# Carrier-Board-CM740.net
KiCad netlist of a schematic drawn in EAGLE
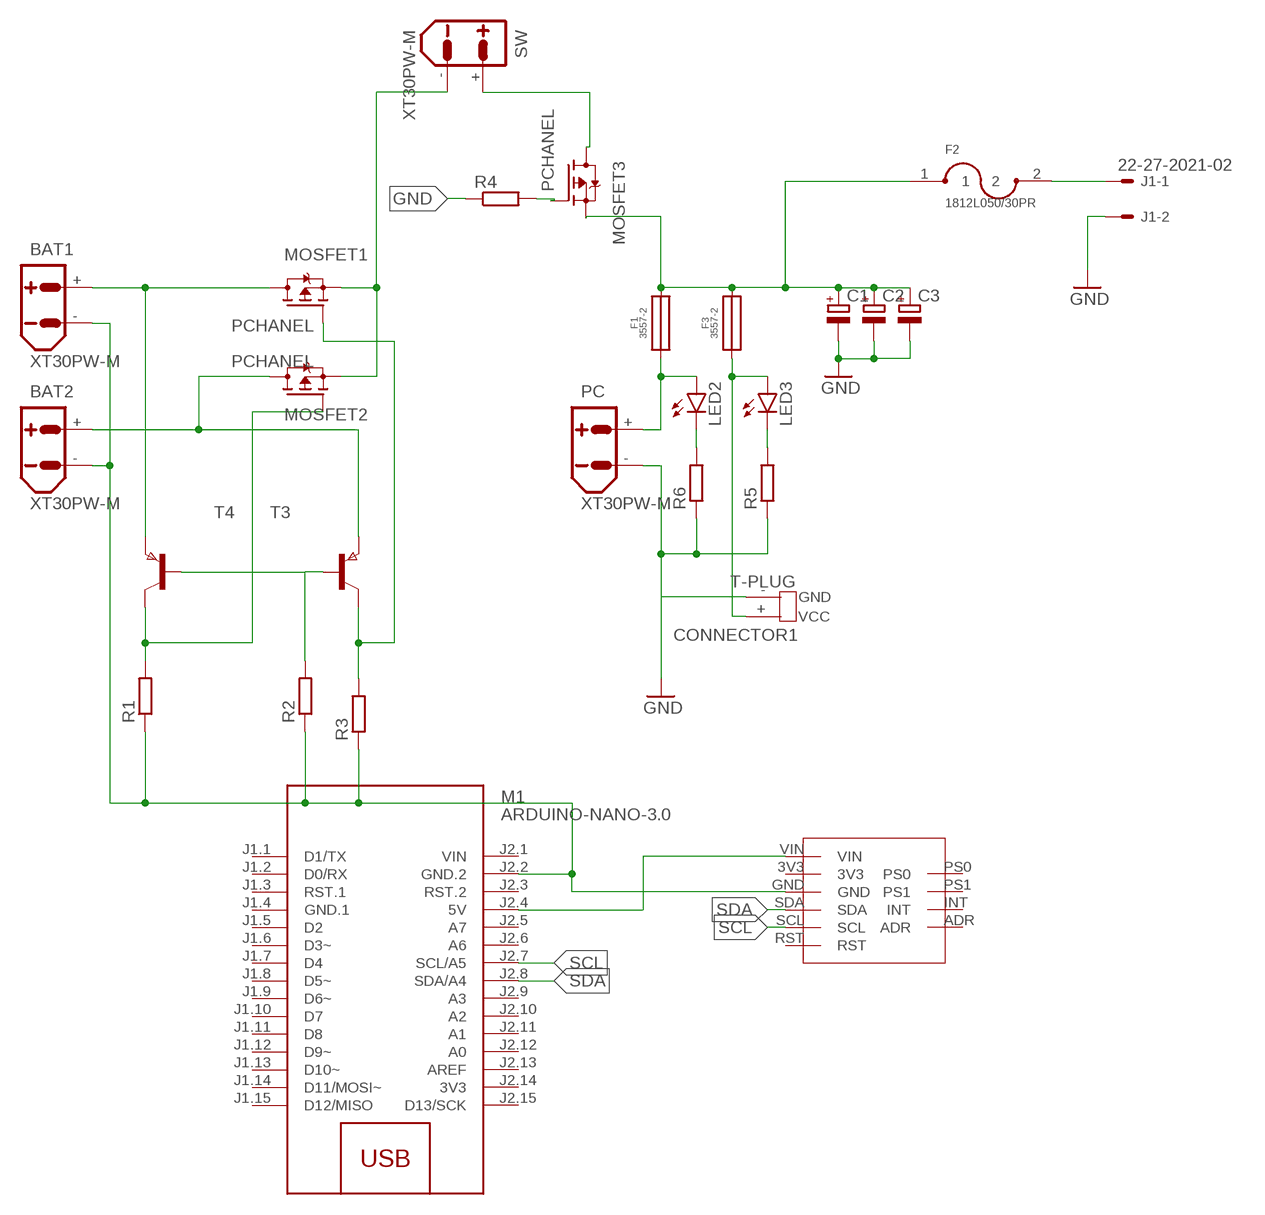
[diagram p0: schematic, sheet 1]

(export (version "E")
  (design (tool "Eeschema 10.0.6"))
  (components
    (comp (ref "BAT1")
      (value "XT30PW-M")
      (footprint "eagle-import:XT30PW-M")
      (libsource (lib "eagle-import") (part "XT30PW-M"))
    )
    (comp (ref "BAT2")
      (value "XT30PW-M")
      (footprint "eagle-import:XT30PW-M")
      (libsource (lib "eagle-import") (part "XT30PW-M"))
    )
    (comp (ref "C1")
      (value "CPOL-EU150CLZ-1014")
      (footprint "eagle-import:150CLZ-1014")
      (libsource (lib "eagle-import") (part "CPOL-EU150CLZ-1014"))
    )
    (comp (ref "C2")
      (value "CPOL-EU150CLZ-1014")
      (footprint "eagle-import:150CLZ-1014")
      (libsource (lib "eagle-import") (part "CPOL-EU150CLZ-1014"))
    )
    (comp (ref "C3")
      (value "CPOL-EU150CLZ-1014")
      (footprint "eagle-import:150CLZ-1014")
      (libsource (lib "eagle-import") (part "CPOL-EU150CLZ-1014"))
    )
    (comp (ref "CONNECTOR1")
      (value "T-PLUG")
      (footprint "eagle-import:T-PLUG")
      (libsource (lib "eagle-import") (part "T-PLUG"))
    )
    (comp (ref "F1")
      (value "3557-2")
      (footprint "eagle-import:3557-2")
      (libsource (lib "eagle-import") (part "3557-2"))
    )
    (comp (ref "F2")
      (value "1812L050/30PR")
      (footprint "eagle-import:FUSM4632X75")
      (fields (field (name "MF") "Littelfuse"))
      (libsource (lib "eagle-import") (part "1812L050/30PR"))
    )
    (comp (ref "F3")
      (value "3557-2")
      (footprint "eagle-import:3557-2")
      (libsource (lib "eagle-import") (part "3557-2"))
    )
    (comp (ref "J1")
      (value "22-27-2021-02")
      (footprint "eagle-import:6410-02")
      (fields (field (name "MF") "MOLEX"))
      (libsource (lib "eagle-import") (part "22-?-0227-2021"))
    )
    (comp (ref "LED2")
      (value "LEDCHIP-LED0805")
      (footprint "eagle-import:CHIP-LED0805")
      (libsource (lib "eagle-import") (part "LEDCHIP-LED0805"))
    )
    (comp (ref "LED3")
      (value "LEDCHIP-LED0805")
      (footprint "eagle-import:CHIP-LED0805")
      (libsource (lib "eagle-import") (part "LEDCHIP-LED0805"))
    )
    (comp (ref "M1")
      (value "ARDUINO-NANO-3.0")
      (footprint "eagle-import:ARDUINO-NANO-3.0")
      (libsource (lib "eagle-import") (part "ARDUINO-NANO-3.0"))
    )
    (comp (ref "MOSFET1")
      (value "PCHANEL")
      (footprint "eagle-import:TO252")
      (libsource (lib "eagle-import") (part "FDD4141TO252"))
    )
    (comp (ref "MOSFET2")
      (value "PCHANEL")
      (footprint "eagle-import:TO252")
      (libsource (lib "eagle-import") (part "FDD4141TO252"))
    )
    (comp (ref "MOSFET3")
      (value "PCHANEL")
      (footprint "eagle-import:TO252")
      (libsource (lib "eagle-import") (part "FDD4141TO252"))
    )
    (comp (ref "PC")
      (value "XT30PW-M")
      (footprint "eagle-import:XT30PW-M")
      (libsource (lib "eagle-import") (part "XT30PW-M"))
    )
    (comp (ref "R1")
      (value "R-EU_R1206")
      (footprint "eagle-import:R1206")
      (libsource (lib "eagle-import") (part "R-EU_R1206"))
    )
    (comp (ref "R2")
      (value "R-EU_R1206")
      (footprint "eagle-import:R1206")
      (libsource (lib "eagle-import") (part "R-EU_R1206"))
    )
    (comp (ref "R3")
      (value "R-EU_R1206")
      (footprint "eagle-import:R1206")
      (libsource (lib "eagle-import") (part "R-EU_R1206"))
    )
    (comp (ref "R4")
      (value "R-EU_R1206")
      (footprint "eagle-import:R1206")
      (libsource (lib "eagle-import") (part "R-EU_R1206"))
    )
    (comp (ref "R5")
      (value "R-EU_M0805")
      (footprint "eagle-import:M0805")
      (libsource (lib "eagle-import") (part "R-EU_M0805"))
    )
    (comp (ref "R6")
      (value "R-EU_M0805")
      (footprint "eagle-import:M0805")
      (libsource (lib "eagle-import") (part "R-EU_M0805"))
    )
    (comp (ref "SW")
      (value "XT30PW-M")
      (footprint "eagle-import:XT30PW-M")
      (libsource (lib "eagle-import") (part "XT30PW-M"))
    )
    (comp (ref "T3")
      (value "PNPSOT23")
      (footprint "eagle-import:SOT-23")
      (fields (field (name "MPN") "DSS20200L-7"))
      (libsource (lib "eagle-import") (part "PNPSOT23"))
    )
    (comp (ref "T4")
      (value "PNPSOT23")
      (footprint "eagle-import:SOT-23")
      (fields (field (name "MPN") "DSS20200L-7"))
      (libsource (lib "eagle-import") (part "PNPSOT23"))
    )
    (comp (ref "U$1")
      (value "BNO055_BNO055")
      (footprint "eagle-import:BNO055_BNO055")
      (libsource (lib "eagle-import") (part "BNO055_BNO055"))
    )
  )
  (nets
    (net (code "1") (name "/3V3") (class "Default")
      (node (ref "M1") (pin "J2.14") (pinfunction "3V3_J2.14") (pintype "power_in"))
    )
    (net (code "2") (name "/GND.1") (class "Default")
      (node (ref "M1") (pin "J1.4") (pinfunction "GND.1_J1.4") (pintype "power_in"))
    )
    (net (code "3") (name "/VIN") (class "Default")
      (node (ref "M1") (pin "J2.1") (pinfunction "VIN_J2.1") (pintype "power_in"))
    )
    (net (code "4") (name "GND") (class "Default")
      (node (ref "BAT1") (pin "-") (pinfunction "-_-") (pintype "power_in"))
      (node (ref "BAT2") (pin "-") (pinfunction "-_-") (pintype "power_in"))
      (node (ref "C1") (pin "-") (pinfunction "-_-") (pintype "passive"))
      (node (ref "C2") (pin "-") (pinfunction "-_-") (pintype "passive"))
      (node (ref "C3") (pin "-") (pinfunction "-_-") (pintype "passive"))
      (node (ref "CONNECTOR1") (pin "-") (pinfunction "GND_-") (pintype "power_in"))
      (node (ref "J1") (pin "2") (pinfunction "S_2") (pintype "passive"))
      (node (ref "M1") (pin "J2.2") (pinfunction "GND.2_J2.2") (pintype "power_in"))
      (node (ref "PC") (pin "-") (pinfunction "-_-") (pintype "power_in"))
      (node (ref "R1") (pin "1") (pinfunction "1_1") (pintype "passive"))
      (node (ref "R2") (pin "1") (pinfunction "1_1") (pintype "passive"))
      (node (ref "R3") (pin "1") (pinfunction "1_1") (pintype "passive"))
      (node (ref "R4") (pin "1") (pinfunction "1_1") (pintype "passive"))
      (node (ref "R5") (pin "1") (pinfunction "1_1") (pintype "passive"))
      (node (ref "R6") (pin "1") (pinfunction "1_1") (pintype "passive"))
      (node (ref "U$1") (pin "GND") (pinfunction "GND_GND") (pintype "bidirectional"))
    )
    (net (code "5") (name "Net-(CONNECTOR1-VCC)") (class "Default")
      (node (ref "CONNECTOR1") (pin "+") (pinfunction "VCC_+") (pintype "power_in"))
      (node (ref "F3") (pin "1") (pinfunction "1_1") (pintype "bidirectional"))
      (node (ref "F3") (pin "2") (pinfunction "1_2") (pintype "bidirectional"))
      (node (ref "LED3") (pin "A") (pinfunction "A_A") (pintype "passive"))
    )
    (net (code "6") (name "Net-(F1-1-Pad2)") (class "Default")
      (node (ref "F1") (pin "1") (pinfunction "1_1") (pintype "bidirectional"))
      (node (ref "F1") (pin "2") (pinfunction "1_2") (pintype "bidirectional"))
      (node (ref "LED2") (pin "A") (pinfunction "A_A") (pintype "passive"))
      (node (ref "PC") (pin "+") (pinfunction "+_+") (pintype "power_in"))
    )
    (net (code "7") (name "Net-(J1A-S)") (class "Default")
      (node (ref "F2") (pin "2") (pinfunction "2_2") (pintype "passive"))
      (node (ref "J1") (pin "1") (pinfunction "S_1") (pintype "passive"))
    )
    (net (code "8") (name "Net-(LED2-PadC)") (class "Default")
      (node (ref "LED2") (pin "C") (pinfunction "C_C") (pintype "passive"))
      (node (ref "R6") (pin "2") (pinfunction "2_2") (pintype "passive"))
    )
    (net (code "9") (name "Net-(LED3-PadC)") (class "Default")
      (node (ref "LED3") (pin "C") (pinfunction "C_C") (pintype "passive"))
      (node (ref "R5") (pin "2") (pinfunction "2_2") (pintype "passive"))
    )
    (net (code "10") (name "Net-(M1-5V)") (class "Default")
      (node (ref "M1") (pin "J2.4") (pinfunction "5V_J2.4") (pintype "power_in"))
      (node (ref "U$1") (pin "VIN") (pinfunction "VIN_VIN") (pintype "bidirectional"))
    )
    (net (code "11") (name "Net-(MOSFET1-D)") (class "Default")
      (node (ref "BAT1") (pin "+") (pinfunction "+_+") (pintype "power_in"))
      (node (ref "MOSFET1") (pin "3") (pinfunction "D_3") (pintype "passive"))
      (node (ref "T4") (pin "2") (pinfunction "E_2") (pintype "passive"))
    )
    (net (code "12") (name "Net-(MOSFET1-G)") (class "Default")
      (node (ref "MOSFET1") (pin "1") (pinfunction "G_1") (pintype "passive"))
      (node (ref "R3") (pin "2") (pinfunction "2_2") (pintype "passive"))
      (node (ref "T3") (pin "1") (pinfunction "C_1") (pintype "passive"))
    )
    (net (code "13") (name "Net-(MOSFET1-S)") (class "Default")
      (node (ref "MOSFET1") (pin "2") (pinfunction "S_2") (pintype "passive"))
      (node (ref "MOSFET2") (pin "2") (pinfunction "S_2") (pintype "passive"))
      (node (ref "SW") (pin "-") (pinfunction "-_-") (pintype "power_in"))
    )
    (net (code "14") (name "Net-(MOSFET2-D)") (class "Default")
      (node (ref "BAT2") (pin "+") (pinfunction "+_+") (pintype "power_in"))
      (node (ref "MOSFET2") (pin "3") (pinfunction "D_3") (pintype "passive"))
      (node (ref "T3") (pin "2") (pinfunction "E_2") (pintype "passive"))
    )
    (net (code "15") (name "Net-(MOSFET2-G)") (class "Default")
      (node (ref "MOSFET2") (pin "1") (pinfunction "G_1") (pintype "passive"))
      (node (ref "R1") (pin "2") (pinfunction "2_2") (pintype "passive"))
      (node (ref "T4") (pin "1") (pinfunction "C_1") (pintype "passive"))
    )
    (net (code "16") (name "Net-(MOSFET3-D)") (class "Default")
      (node (ref "MOSFET3") (pin "3") (pinfunction "D_3") (pintype "passive"))
      (node (ref "SW") (pin "+") (pinfunction "+_+") (pintype "power_in"))
    )
    (net (code "17") (name "Net-(MOSFET3-G)") (class "Default")
      (node (ref "MOSFET3") (pin "1") (pinfunction "G_1") (pintype "passive"))
      (node (ref "R4") (pin "2") (pinfunction "2_2") (pintype "passive"))
    )
    (net (code "18") (name "Net-(MOSFET3-S)") (class "Default")
      (node (ref "C1") (pin "+") (pinfunction "+_+") (pintype "passive"))
      (node (ref "C2") (pin "+") (pinfunction "+_+") (pintype "passive"))
      (node (ref "C3") (pin "+") (pinfunction "+_+") (pintype "passive"))
      (node (ref "F1") (pin "3") (pinfunction "2_3") (pintype "bidirectional"))
      (node (ref "F1") (pin "4") (pinfunction "2_4") (pintype "bidirectional"))
      (node (ref "F2") (pin "1") (pinfunction "1_1") (pintype "passive"))
      (node (ref "F3") (pin "3") (pinfunction "2_3") (pintype "bidirectional"))
      (node (ref "F3") (pin "4") (pinfunction "2_4") (pintype "bidirectional"))
      (node (ref "MOSFET3") (pin "2") (pinfunction "S_2") (pintype "passive"))
    )
    (net (code "19") (name "Net-(T3-B)") (class "Default")
      (node (ref "R2") (pin "2") (pinfunction "2_2") (pintype "passive"))
      (node (ref "T3") (pin "3") (pinfunction "B_3") (pintype "passive"))
      (node (ref "T4") (pin "3") (pinfunction "B_3") (pintype "passive"))
    )
    (net (code "20") (name "SCL") (class "Default")
      (node (ref "M1") (pin "J2.7") (pinfunction "SCL/A5_J2.7") (pintype "bidirectional"))
      (node (ref "U$1") (pin "SCL") (pinfunction "SCL_SCL") (pintype "bidirectional"))
    )
    (net (code "21") (name "SDA") (class "Default")
      (node (ref "M1") (pin "J2.8") (pinfunction "SDA/A4_J2.8") (pintype "bidirectional"))
      (node (ref "U$1") (pin "SDA") (pinfunction "SDA_SDA") (pintype "bidirectional"))
    )
    (net (code "22") (name "unconnected-(M1-A0-PadJ2.12)") (class "Default")
      (node (ref "M1") (pin "J2.12") (pinfunction "A0_J2.12") (pintype "bidirectional"))
    )
    (net (code "23") (name "unconnected-(M1-A1-PadJ2.11)") (class "Default")
      (node (ref "M1") (pin "J2.11") (pinfunction "A1_J2.11") (pintype "bidirectional"))
    )
    (net (code "24") (name "unconnected-(M1-A2-PadJ2.10)") (class "Default")
      (node (ref "M1") (pin "J2.10") (pinfunction "A2_J2.10") (pintype "bidirectional"))
    )
    (net (code "25") (name "unconnected-(M1-A3-PadJ2.9)") (class "Default")
      (node (ref "M1") (pin "J2.9") (pinfunction "A3_J2.9") (pintype "bidirectional"))
    )
    (net (code "26") (name "unconnected-(M1-A6-PadJ2.6)") (class "Default")
      (node (ref "M1") (pin "J2.6") (pinfunction "A6_J2.6") (pintype "bidirectional"))
    )
    (net (code "27") (name "unconnected-(M1-A7-PadJ2.5)") (class "Default")
      (node (ref "M1") (pin "J2.5") (pinfunction "A7_J2.5") (pintype "bidirectional"))
    )
    (net (code "28") (name "unconnected-(M1-AREF-PadJ2.13)") (class "Default")
      (node (ref "M1") (pin "J2.13") (pinfunction "AREF_J2.13") (pintype "bidirectional"))
    )
    (net (code "29") (name "unconnected-(M1-D0{slash}RX-PadJ1.2)") (class "Default")
      (node (ref "M1") (pin "J1.2") (pinfunction "D0/RX_J1.2") (pintype "bidirectional"))
    )
    (net (code "30") (name "unconnected-(M1-D1{slash}TX-PadJ1.1)") (class "Default")
      (node (ref "M1") (pin "J1.1") (pinfunction "D1/TX_J1.1") (pintype "bidirectional"))
    )
    (net (code "31") (name "unconnected-(M1-D2-PadJ1.5)") (class "Default")
      (node (ref "M1") (pin "J1.5") (pinfunction "D2_J1.5") (pintype "bidirectional"))
    )
    (net (code "32") (name "unconnected-(M1-D3~{}-PadJ1.6)") (class "Default")
      (node (ref "M1") (pin "J1.6") (pinfunction "D3~{}_J1.6") (pintype "bidirectional"))
    )
    (net (code "33") (name "unconnected-(M1-D4-PadJ1.7)") (class "Default")
      (node (ref "M1") (pin "J1.7") (pinfunction "D4_J1.7") (pintype "bidirectional"))
    )
    (net (code "34") (name "unconnected-(M1-D5~{}-PadJ1.8)") (class "Default")
      (node (ref "M1") (pin "J1.8") (pinfunction "D5~{}_J1.8") (pintype "bidirectional"))
    )
    (net (code "35") (name "unconnected-(M1-D6~{}-PadJ1.9)") (class "Default")
      (node (ref "M1") (pin "J1.9") (pinfunction "D6~{}_J1.9") (pintype "bidirectional"))
    )
    (net (code "36") (name "unconnected-(M1-D7-PadJ1.10)") (class "Default")
      (node (ref "M1") (pin "J1.10") (pinfunction "D7_J1.10") (pintype "bidirectional"))
    )
    (net (code "37") (name "unconnected-(M1-D8-PadJ1.11)") (class "Default")
      (node (ref "M1") (pin "J1.11") (pinfunction "D8_J1.11") (pintype "bidirectional"))
    )
    (net (code "38") (name "unconnected-(M1-D9~{}-PadJ1.12)") (class "Default")
      (node (ref "M1") (pin "J1.12") (pinfunction "D9~{}_J1.12") (pintype "bidirectional"))
    )
    (net (code "39") (name "unconnected-(M1-D10~{}-PadJ1.13)") (class "Default")
      (node (ref "M1") (pin "J1.13") (pinfunction "D10~{}_J1.13") (pintype "bidirectional"))
    )
    (net (code "40") (name "unconnected-(M1-D11{slash}MOSI~{}-PadJ1.14)") (class "Default")
      (node (ref "M1") (pin "J1.14") (pinfunction "D11/MOSI~{}_J1.14") (pintype "bidirectional"))
    )
    (net (code "41") (name "unconnected-(M1-D12{slash}MISO-PadJ1.15)") (class "Default")
      (node (ref "M1") (pin "J1.15") (pinfunction "D12/MISO_J1.15") (pintype "bidirectional"))
    )
    (net (code "42") (name "unconnected-(M1-D13{slash}SCK-PadJ2.15)") (class "Default")
      (node (ref "M1") (pin "J2.15") (pinfunction "D13/SCK_J2.15") (pintype "bidirectional"))
    )
    (net (code "43") (name "unconnected-(M1-RST.1-PadJ1.3)") (class "Default")
      (node (ref "M1") (pin "J1.3") (pinfunction "RST.1_J1.3") (pintype "bidirectional"))
    )
    (net (code "44") (name "unconnected-(M1-RST.2-PadJ2.3)") (class "Default")
      (node (ref "M1") (pin "J2.3") (pinfunction "RST.2_J2.3") (pintype "bidirectional"))
    )
    (net (code "45") (name "unconnected-(U$1-Pad3V3)") (class "Default")
      (node (ref "U$1") (pin "3V3") (pinfunction "3V3_3V3") (pintype "bidirectional"))
    )
    (net (code "46") (name "unconnected-(U$1-PadADR)") (class "Default")
      (node (ref "U$1") (pin "ADR") (pinfunction "ADR_ADR") (pintype "bidirectional"))
    )
    (net (code "47") (name "unconnected-(U$1-PadINT)") (class "Default")
      (node (ref "U$1") (pin "INT") (pinfunction "INT_INT") (pintype "bidirectional"))
    )
    (net (code "48") (name "unconnected-(U$1-PadPS0)") (class "Default")
      (node (ref "U$1") (pin "PS0") (pinfunction "PS0_PS0") (pintype "bidirectional"))
    )
    (net (code "49") (name "unconnected-(U$1-PadPS1)") (class "Default")
      (node (ref "U$1") (pin "PS1") (pinfunction "PS1_PS1") (pintype "bidirectional"))
    )
    (net (code "50") (name "unconnected-(U$1-PadRST)") (class "Default")
      (node (ref "U$1") (pin "RST") (pinfunction "RST_RST") (pintype "bidirectional"))
    )
  )
)
